# femtobuck.net
KiCad netlist of a schematic drawn in EAGLE
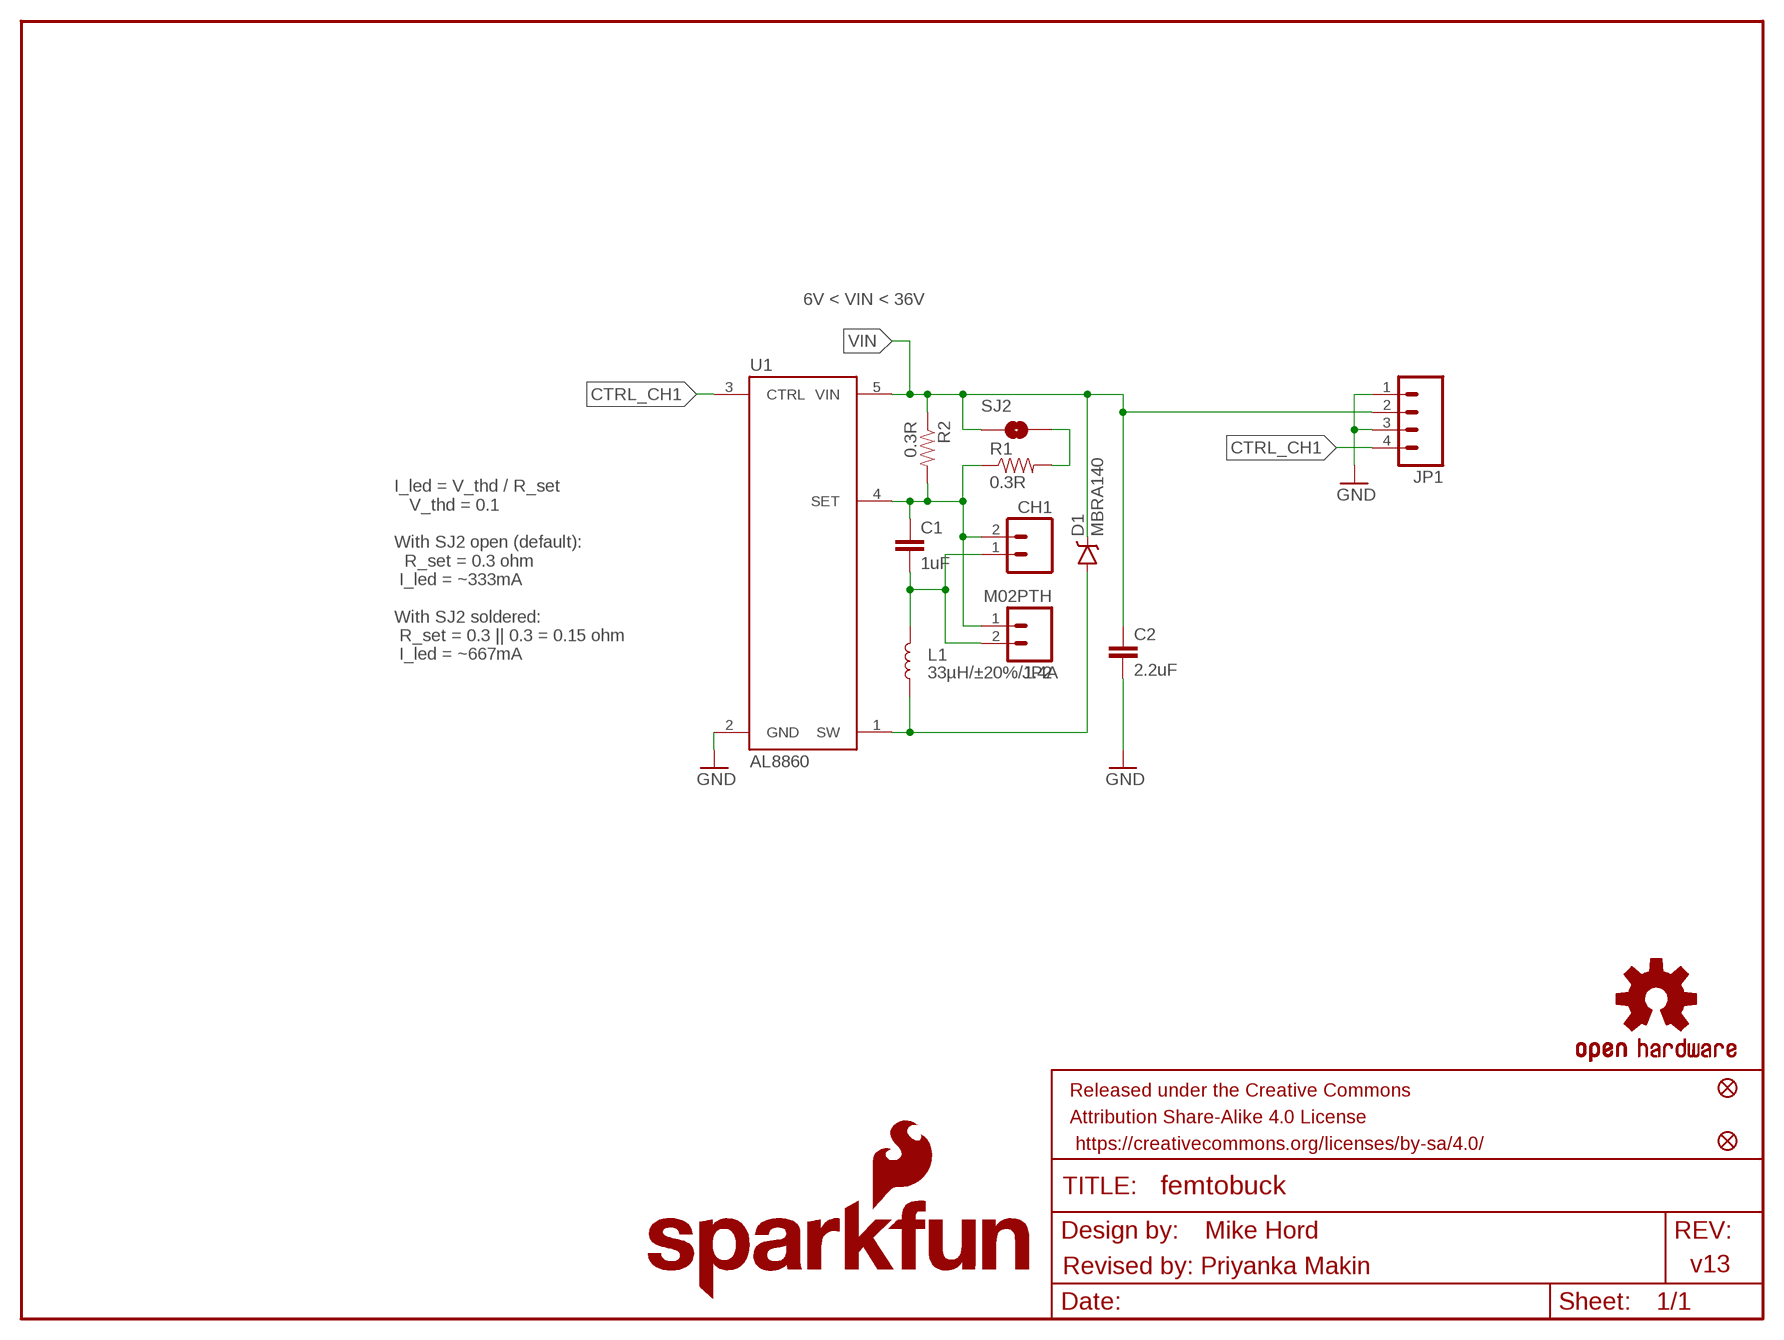
[diagram p0: schematic, sheet 1]

(export (version "E")
  (design (tool "Eeschema 10.0.6"))
  (components
    (comp (ref "C1")
      (value "1uF")
      (footprint "eagle-import:1206-CAP")
      (libsource (lib "eagle-import") (part "1.0UF50V10%(1206)"))
    )
    (comp (ref "C2")
      (value "2.2uF")
      (footprint "eagle-import:1206-CAP")
      (libsource (lib "eagle-import") (part "2.2UF50V10%(1206)"))
    )
    (comp (ref "CH1")
      (value "CONN_023.5MM_LOCK")
      (footprint "eagle-import:SCREWTERMINAL-3.5MM-2_LOCK")
      (libsource (lib "eagle-import") (part "CONN_023.5MM_LOCK"))
    )
    (comp (ref "D1")
      (value "MBRA140")
      (footprint "eagle-import:SMA-DIODE")
      (libsource (lib "eagle-import") (part "DIODE-SCHOTTKY-MBRA140"))
    )
    (comp (ref "FID1")
      (value "FIDUCIAL1X2")
      (footprint "eagle-import:FIDUCIAL-1X2")
      (libsource (lib "eagle-import") (part "FIDUCIAL1X2"))
    )
    (comp (ref "FID2")
      (value "FIDUCIAL1X2")
      (footprint "eagle-import:FIDUCIAL-1X2")
      (libsource (lib "eagle-import") (part "FIDUCIAL1X2"))
    )
    (comp (ref "FRAME1")
      (value "FRAME-LETTER")
      (footprint "eagle-import:CREATIVE_COMMONS")
      (libsource (lib "eagle-import") (part "FRAME-LETTER"))
    )
    (comp (ref "JP1")
      (value "M04PTH")
      (footprint "eagle-import:1X04")
      (libsource (lib "eagle-import") (part "M04PTH"))
    )
    (comp (ref "JP2")
      (value "M02PTH")
      (footprint "eagle-import:1X02@1")
      (libsource (lib "eagle-import") (part "M02PTH"))
    )
    (comp (ref "L1")
      (value "33µH/±20%/1.4A")
      (footprint "eagle-import:SRN6045")
      (libsource (lib "eagle-import") (part "INDUCTOR-SRN6045-33UH"))
    )
    (comp (ref "LOGO1")
      (value "OSHW-LOGOS")
      (footprint "eagle-import:OSHW-LOGO-S")
      (libsource (lib "eagle-import") (part "OSHW-LOGOS"))
    )
    (comp (ref "LOGO2")
      (value "SFE_LOGO_NAME_FLAME.1_INCH")
      (footprint "eagle-import:SFE_LOGO_NAME_FLAME_.1")
      (libsource (lib "eagle-import") (part "SFE_LOGO_NAME_FLAME.1_INCH"))
    )
    (comp (ref "R1")
      (value "0.3R")
      (footprint "eagle-import:0805")
      (libsource (lib "eagle-import") (part "0.3OHM-1/8W-1%(0805)"))
    )
    (comp (ref "R2")
      (value "0.3R")
      (footprint "eagle-import:0805")
      (libsource (lib "eagle-import") (part "0.3OHM-1/8W-1%(0805)"))
    )
    (comp (ref "SJ2")
      (value "NO Jumper")
      (footprint "eagle-import:SMT-JUMPER_2_NO_NO-SILK")
      (libsource (lib "eagle-import") (part "JUMPER-SMT_2_NO_NO-SILK"))
    )
    (comp (ref "U1")
      (value "AL8860")
      (footprint "eagle-import:SOT23-5")
      (libsource (lib "eagle-import") (part "AL8860"))
    )
  )
  (nets
    (net (code "1") (name "CTRL_CH1") (class "Default")
      (node (ref "JP1") (pin "4") (pinfunction "4_4") (pintype "passive"))
      (node (ref "U1") (pin "3") (pinfunction "CTRL_3") (pintype "bidirectional"))
    )
    (net (code "2") (name "GND") (class "Default")
      (node (ref "C2") (pin "2") (pinfunction "2_2") (pintype "passive"))
      (node (ref "JP1") (pin "1") (pinfunction "1_1") (pintype "passive"))
      (node (ref "JP1") (pin "3") (pinfunction "3_3") (pintype "passive"))
      (node (ref "U1") (pin "2") (pinfunction "GND_2") (pintype "bidirectional"))
    )
    (net (code "3") (name "Net-(C1-Pad2)") (class "Default")
      (node (ref "C1") (pin "2") (pinfunction "2_2") (pintype "passive"))
      (node (ref "CH1") (pin "1") (pinfunction "1_1") (pintype "passive"))
      (node (ref "JP2") (pin "2") (pinfunction "2_2") (pintype "passive"))
      (node (ref "L1") (pin "2") (pinfunction "2_2") (pintype "passive"))
    )
    (net (code "4") (name "Net-(R1-Pad2)") (class "Default")
      (node (ref "R1") (pin "2") (pinfunction "2_2") (pintype "passive"))
      (node (ref "SJ2") (pin "2") (pinfunction "2_2") (pintype "passive"))
    )
    (net (code "5") (name "Net-(U1-SET)") (class "Default")
      (node (ref "C1") (pin "1") (pinfunction "1_1") (pintype "passive"))
      (node (ref "CH1") (pin "2") (pinfunction "2_2") (pintype "passive"))
      (node (ref "JP2") (pin "1") (pinfunction "1_1") (pintype "passive"))
      (node (ref "R1") (pin "1") (pinfunction "1_1") (pintype "passive"))
      (node (ref "R2") (pin "2") (pinfunction "2_2") (pintype "passive"))
      (node (ref "U1") (pin "4") (pinfunction "SET_4") (pintype "bidirectional"))
    )
    (net (code "6") (name "Net-(U1-SW)") (class "Default")
      (node (ref "D1") (pin "A") (pinfunction "A_A") (pintype "passive"))
      (node (ref "L1") (pin "1") (pinfunction "1_1") (pintype "passive"))
      (node (ref "U1") (pin "1") (pinfunction "SW_1") (pintype "bidirectional"))
    )
    (net (code "7") (name "VIN") (class "Default")
      (node (ref "C2") (pin "1") (pinfunction "1_1") (pintype "passive"))
      (node (ref "D1") (pin "C") (pinfunction "C_C") (pintype "passive"))
      (node (ref "JP1") (pin "2") (pinfunction "2_2") (pintype "passive"))
      (node (ref "R2") (pin "1") (pinfunction "1_1") (pintype "passive"))
      (node (ref "SJ2") (pin "1") (pinfunction "1_1") (pintype "passive"))
      (node (ref "U1") (pin "5") (pinfunction "VIN_5") (pintype "bidirectional"))
    )
  )
)
